# Micro_SD_Block.net
KiCad netlist of a schematic drawn in EAGLE
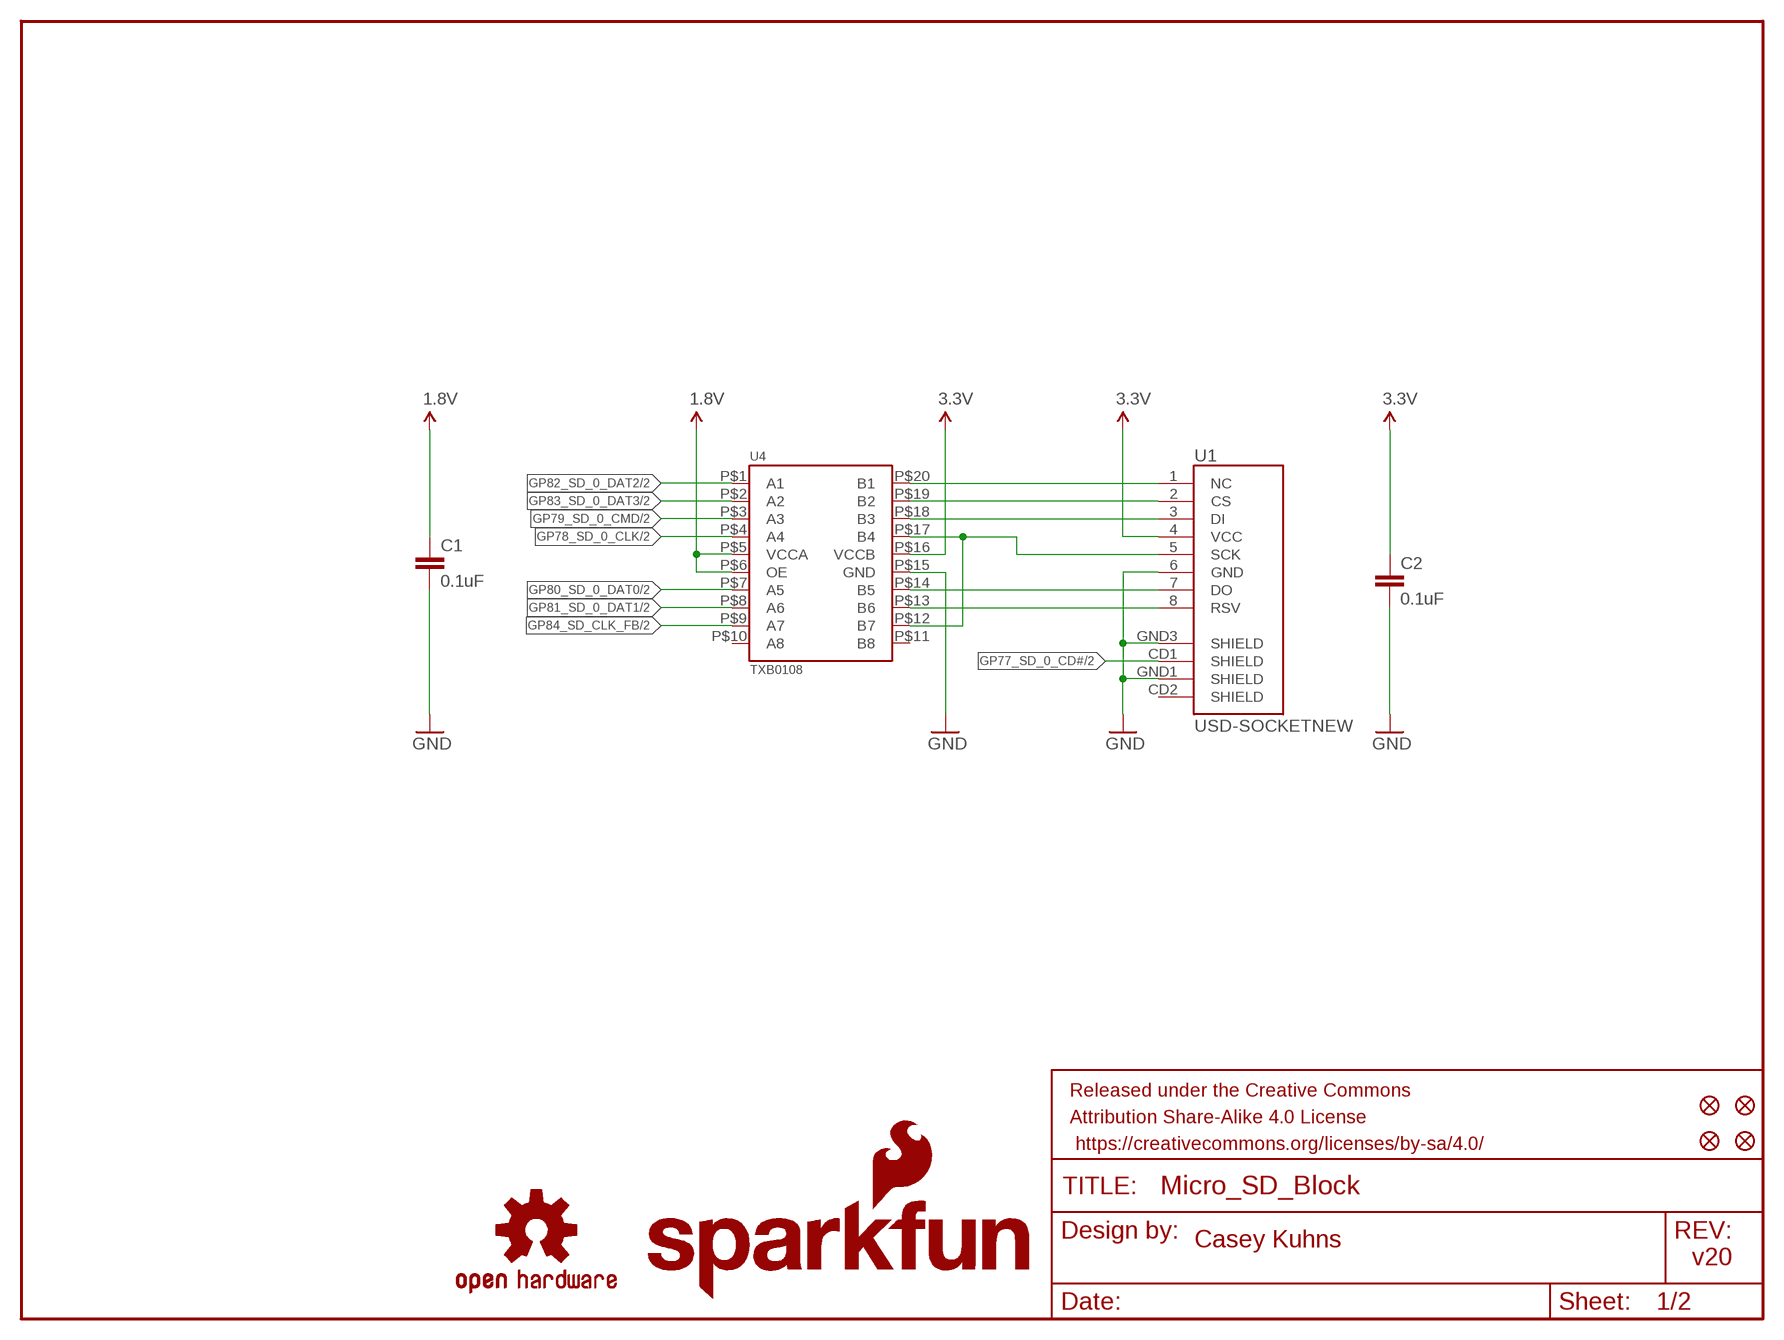
[diagram p0: schematic, sheet 1]
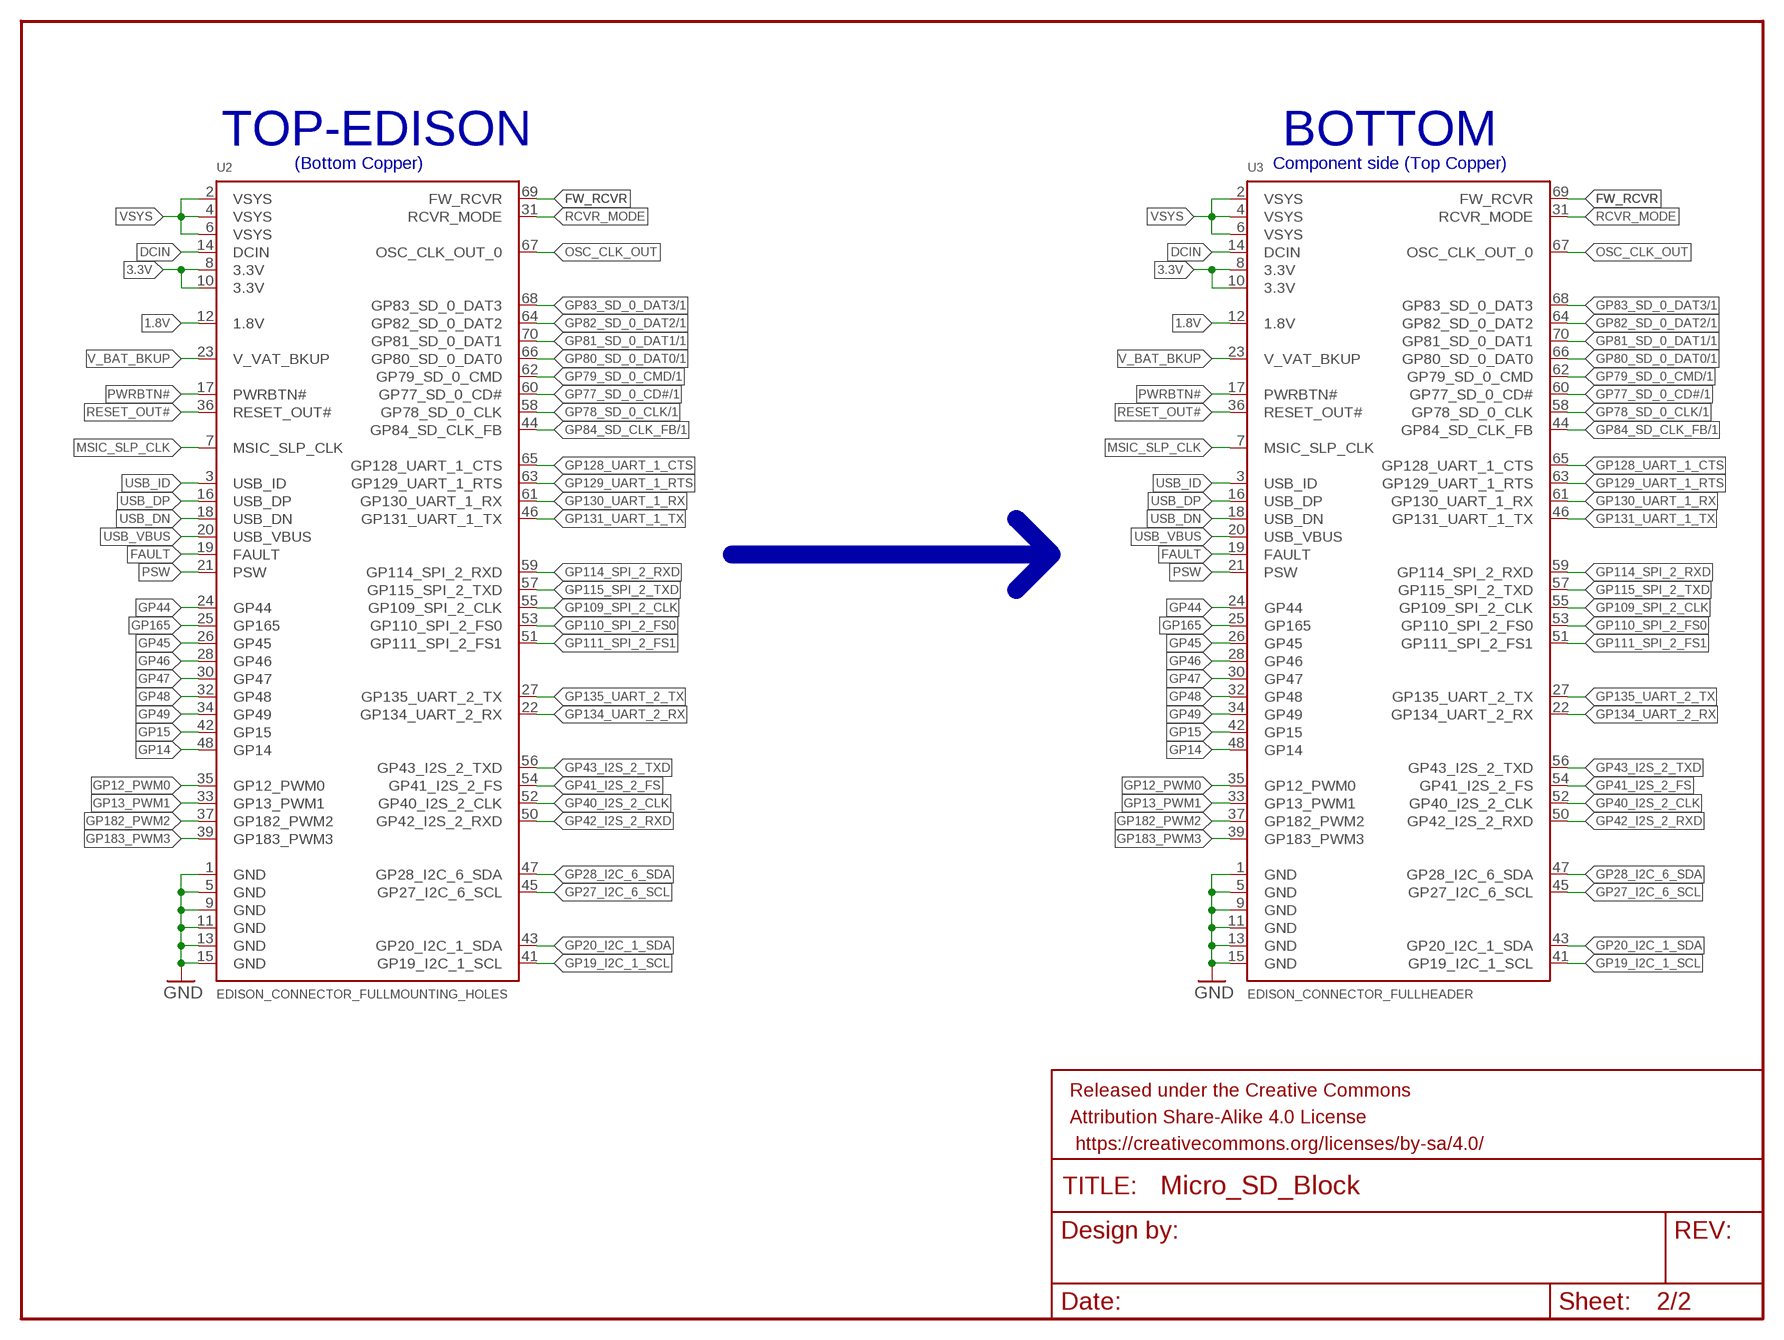
[diagram p1: schematic, sheet 2]

(export (version "E")
  (design (tool "Eeschema 10.0.6"))
  (components
    (comp (ref "C1")
      (value "0.1uF")
      (footprint "eagle-import:0603-CAP")
      (libsource (lib "eagle-import") (part "0.1UF-25V(+80/-20%)(0603)"))
    )
    (comp (ref "C2")
      (value "0.1uF")
      (footprint "eagle-import:0603-CAP")
      (libsource (lib "eagle-import") (part "0.1UF-25V(+80/-20%)(0603)"))
    )
    (comp (ref "FID1")
      (value "FIDUCIAL1X2")
      (footprint "eagle-import:FIDUCIAL-1X2")
      (libsource (lib "eagle-import") (part "FIDUCIAL1X2"))
    )
    (comp (ref "FID2")
      (value "FIDUCIAL1X2")
      (footprint "eagle-import:FIDUCIAL-1X2")
      (libsource (lib "eagle-import") (part "FIDUCIAL1X2"))
    )
    (comp (ref "FID3")
      (value "FIDUCIAL1X2")
      (footprint "eagle-import:FIDUCIAL-1X2")
      (libsource (lib "eagle-import") (part "FIDUCIAL1X2"))
    )
    (comp (ref "FID4")
      (value "FIDUCIAL1X2")
      (footprint "eagle-import:FIDUCIAL-1X2")
      (libsource (lib "eagle-import") (part "FIDUCIAL1X2"))
    )
    (comp (ref "FRAME1")
      (value "FRAME-LETTER")
      (footprint "eagle-import:CREATIVE_COMMONS")
      (libsource (lib "eagle-import") (part "FRAME-LETTER"))
    )
    (comp (ref "LOGO1")
      (value "OSHW-LOGOS")
      (footprint "eagle-import:OSHW-LOGO-S")
      (libsource (lib "eagle-import") (part "OSHW-LOGOS"))
    )
    (comp (ref "LOGO4")
      (value "SFE_LOGO_NAME_FLAME.1_INCH")
      (footprint "eagle-import:SFE_LOGO_NAME_FLAME_.1")
      (libsource (lib "eagle-import") (part "SFE_LOGO_NAME_FLAME.1_INCH"))
    )
    (comp (ref "U1")
      (value "USD-SOCKETNEW")
      (footprint "eagle-import:MICRO-SD-SOCKET-PP")
      (libsource (lib "eagle-import") (part "USD-SOCKETNEW"))
    )
    (comp (ref "U4")
      (value "TXB0108")
      (footprint "eagle-import:UFDFN-20")
      (libsource (lib "eagle-import") (part "TXB0108"))
    )
    (comp (ref "FRAME2")
      (value "FRAME-LETTER")
      (footprint "eagle-import:CREATIVE_COMMONS")
      (libsource (lib "eagle-import") (part "FRAME-LETTER"))
    )
    (comp (ref "U2")
      (value "EDISON_CONNECTOR_FULLMOUNTING_HOLES")
      (footprint "eagle-import:EDISON_DAUGHTER")
      (libsource (lib "eagle-import") (part "EDISON_CONNECTOR_FULLMOUNTING_HOLES"))
    )
    (comp (ref "U3")
      (value "EDISON_CONNECTOR_FULLHEADER")
      (footprint "eagle-import:DF40C-70DP-0.4(51)")
      (libsource (lib "eagle-import") (part "EDISON_CONNECTOR_FULLHEADER"))
    )
  )
  (nets
    (net (code "1") (name "1.8V") (class "Default")
      (node (ref "C1") (pin "1") (pinfunction "1_1") (pintype "passive"))
      (node (ref "U2") (pin "12") (pinfunction "1.8V_12") (pintype "bidirectional"))
      (node (ref "U3") (pin "12") (pinfunction "1.8V_12") (pintype "bidirectional"))
      (node (ref "U4") (pin "P$5") (pinfunction "VCCA_P$5") (pintype "bidirectional"))
      (node (ref "U4") (pin "P$6") (pinfunction "OE_P$6") (pintype "bidirectional"))
    )
    (net (code "2") (name "3.3V") (class "Default")
      (node (ref "C2") (pin "1") (pinfunction "1_1") (pintype "passive"))
      (node (ref "U1") (pin "4") (pinfunction "VCC_4") (pintype "bidirectional"))
      (node (ref "U2") (pin "10") (pinfunction "3.3V_10") (pintype "bidirectional"))
      (node (ref "U2") (pin "8") (pinfunction "3.3V_8") (pintype "bidirectional"))
      (node (ref "U3") (pin "10") (pinfunction "3.3V_10") (pintype "bidirectional"))
      (node (ref "U3") (pin "8") (pinfunction "3.3V_8") (pintype "bidirectional"))
      (node (ref "U4") (pin "P$16") (pinfunction "VCCB_P$16") (pintype "bidirectional"))
    )
    (net (code "3") (name "DCIN") (class "Default")
      (node (ref "U2") (pin "14") (pinfunction "DCIN_14") (pintype "bidirectional"))
      (node (ref "U3") (pin "14") (pinfunction "DCIN_14") (pintype "bidirectional"))
    )
    (net (code "4") (name "FAULT") (class "Default")
      (node (ref "U2") (pin "19") (pinfunction "FAULT_19") (pintype "bidirectional"))
      (node (ref "U3") (pin "19") (pinfunction "FAULT_19") (pintype "bidirectional"))
    )
    (net (code "5") (name "FW_RCVR") (class "Default")
      (node (ref "U2") (pin "69") (pinfunction "FW_RCVR_69") (pintype "bidirectional"))
      (node (ref "U3") (pin "69") (pinfunction "FW_RCVR_69") (pintype "bidirectional"))
    )
    (net (code "6") (name "GND") (class "Default")
      (node (ref "C1") (pin "2") (pinfunction "2_2") (pintype "passive"))
      (node (ref "C2") (pin "2") (pinfunction "2_2") (pintype "passive"))
      (node (ref "U1") (pin "6") (pinfunction "GND_6") (pintype "bidirectional"))
      (node (ref "U1") (pin "GND1") (pinfunction "SHIELD_GND1") (pintype "bidirectional"))
      (node (ref "U1") (pin "GND3") (pinfunction "SHIELD_GND3") (pintype "bidirectional"))
      (node (ref "U2") (pin "1") (pinfunction "GND_1") (pintype "bidirectional"))
      (node (ref "U2") (pin "11") (pinfunction "GND_11") (pintype "bidirectional"))
      (node (ref "U2") (pin "13") (pinfunction "GND_13") (pintype "bidirectional"))
      (node (ref "U2") (pin "15") (pinfunction "GND_15") (pintype "bidirectional"))
      (node (ref "U2") (pin "5") (pinfunction "GND_5") (pintype "bidirectional"))
      (node (ref "U2") (pin "9") (pinfunction "GND_9") (pintype "bidirectional"))
      (node (ref "U3") (pin "1") (pinfunction "GND_1") (pintype "bidirectional"))
      (node (ref "U3") (pin "11") (pinfunction "GND_11") (pintype "bidirectional"))
      (node (ref "U3") (pin "13") (pinfunction "GND_13") (pintype "bidirectional"))
      (node (ref "U3") (pin "15") (pinfunction "GND_15") (pintype "bidirectional"))
      (node (ref "U3") (pin "5") (pinfunction "GND_5") (pintype "bidirectional"))
      (node (ref "U3") (pin "9") (pinfunction "GND_9") (pintype "bidirectional"))
      (node (ref "U4") (pin "P$15") (pinfunction "GND_P$15") (pintype "bidirectional"))
    )
    (net (code "7") (name "GP12_PWM0") (class "Default")
      (node (ref "U2") (pin "35") (pinfunction "GP12_PWM0_35") (pintype "bidirectional"))
      (node (ref "U3") (pin "35") (pinfunction "GP12_PWM0_35") (pintype "bidirectional"))
    )
    (net (code "8") (name "GP13_PWM1") (class "Default")
      (node (ref "U2") (pin "33") (pinfunction "GP13_PWM1_33") (pintype "bidirectional"))
      (node (ref "U3") (pin "33") (pinfunction "GP13_PWM1_33") (pintype "bidirectional"))
    )
    (net (code "9") (name "GP14") (class "Default")
      (node (ref "U2") (pin "48") (pinfunction "GP14_48") (pintype "bidirectional"))
      (node (ref "U3") (pin "48") (pinfunction "GP14_48") (pintype "bidirectional"))
    )
    (net (code "10") (name "GP15") (class "Default")
      (node (ref "U2") (pin "42") (pinfunction "GP15_42") (pintype "bidirectional"))
      (node (ref "U3") (pin "42") (pinfunction "GP15_42") (pintype "bidirectional"))
    )
    (net (code "11") (name "GP19_I2C_1_SCL") (class "Default")
      (node (ref "U2") (pin "41") (pinfunction "GP19_I2C_1_SCL_41") (pintype "bidirectional"))
      (node (ref "U3") (pin "41") (pinfunction "GP19_I2C_1_SCL_41") (pintype "bidirectional"))
    )
    (net (code "12") (name "GP20_I2C_1_SDA") (class "Default")
      (node (ref "U2") (pin "43") (pinfunction "GP20_I2C_1_SDA_43") (pintype "bidirectional"))
      (node (ref "U3") (pin "43") (pinfunction "GP20_I2C_1_SDA_43") (pintype "bidirectional"))
    )
    (net (code "13") (name "GP27_I2C_6_SCL") (class "Default")
      (node (ref "U2") (pin "45") (pinfunction "GP27_I2C_6_SCL_45") (pintype "bidirectional"))
      (node (ref "U3") (pin "45") (pinfunction "GP27_I2C_6_SCL_45") (pintype "bidirectional"))
    )
    (net (code "14") (name "GP28_I2C_6_SDA") (class "Default")
      (node (ref "U2") (pin "47") (pinfunction "GP28_I2C_6_SDA_47") (pintype "bidirectional"))
      (node (ref "U3") (pin "47") (pinfunction "GP28_I2C_6_SDA_47") (pintype "bidirectional"))
    )
    (net (code "15") (name "GP40_I2S_2_CLK") (class "Default")
      (node (ref "U2") (pin "52") (pinfunction "GP40_I2S_2_CLK_52") (pintype "bidirectional"))
      (node (ref "U3") (pin "52") (pinfunction "GP40_I2S_2_CLK_52") (pintype "bidirectional"))
    )
    (net (code "16") (name "GP41_I2S_2_FS") (class "Default")
      (node (ref "U2") (pin "54") (pinfunction "GP41_I2S_2_FS_54") (pintype "bidirectional"))
      (node (ref "U3") (pin "54") (pinfunction "GP41_I2S_2_FS_54") (pintype "bidirectional"))
    )
    (net (code "17") (name "GP42_I2S_2_RXD") (class "Default")
      (node (ref "U2") (pin "50") (pinfunction "GP42_I2S_2_RXD_50") (pintype "bidirectional"))
      (node (ref "U3") (pin "50") (pinfunction "GP42_I2S_2_RXD_50") (pintype "bidirectional"))
    )
    (net (code "18") (name "GP43_I2S_2_TXD") (class "Default")
      (node (ref "U2") (pin "56") (pinfunction "GP43_I2S_2_TXD_56") (pintype "bidirectional"))
      (node (ref "U3") (pin "56") (pinfunction "GP43_I2S_2_TXD_56") (pintype "bidirectional"))
    )
    (net (code "19") (name "GP44") (class "Default")
      (node (ref "U2") (pin "24") (pinfunction "GP44_24") (pintype "bidirectional"))
      (node (ref "U3") (pin "24") (pinfunction "GP44_24") (pintype "bidirectional"))
    )
    (net (code "20") (name "GP45") (class "Default")
      (node (ref "U2") (pin "26") (pinfunction "GP45_26") (pintype "bidirectional"))
      (node (ref "U3") (pin "26") (pinfunction "GP45_26") (pintype "bidirectional"))
    )
    (net (code "21") (name "GP46") (class "Default")
      (node (ref "U2") (pin "28") (pinfunction "GP46_28") (pintype "bidirectional"))
      (node (ref "U3") (pin "28") (pinfunction "GP46_28") (pintype "bidirectional"))
    )
    (net (code "22") (name "GP47") (class "Default")
      (node (ref "U2") (pin "30") (pinfunction "GP47_30") (pintype "bidirectional"))
      (node (ref "U3") (pin "30") (pinfunction "GP47_30") (pintype "bidirectional"))
    )
    (net (code "23") (name "GP48") (class "Default")
      (node (ref "U2") (pin "32") (pinfunction "GP48_32") (pintype "bidirectional"))
      (node (ref "U3") (pin "32") (pinfunction "GP48_32") (pintype "bidirectional"))
    )
    (net (code "24") (name "GP49") (class "Default")
      (node (ref "U2") (pin "34") (pinfunction "GP49_34") (pintype "bidirectional"))
      (node (ref "U3") (pin "34") (pinfunction "GP49_34") (pintype "bidirectional"))
    )
    (net (code "25") (name "GP77_SD_0_CD#") (class "Default")
      (node (ref "U1") (pin "CD1") (pinfunction "SHIELD_CD1") (pintype "bidirectional"))
      (node (ref "U2") (pin "60") (pinfunction "GP77_SD_0_CD#_60") (pintype "bidirectional"))
      (node (ref "U3") (pin "60") (pinfunction "GP77_SD_0_CD#_60") (pintype "bidirectional"))
    )
    (net (code "26") (name "GP78_SD_0_CLK") (class "Default")
      (node (ref "U2") (pin "58") (pinfunction "GP78_SD_0_CLK_58") (pintype "bidirectional"))
      (node (ref "U3") (pin "58") (pinfunction "GP78_SD_0_CLK_58") (pintype "bidirectional"))
      (node (ref "U4") (pin "P$4") (pinfunction "A4_P$4") (pintype "bidirectional"))
    )
    (net (code "27") (name "GP79_SD_0_CMD") (class "Default")
      (node (ref "U2") (pin "62") (pinfunction "GP79_SD_0_CMD_62") (pintype "bidirectional"))
      (node (ref "U3") (pin "62") (pinfunction "GP79_SD_0_CMD_62") (pintype "bidirectional"))
      (node (ref "U4") (pin "P$3") (pinfunction "A3_P$3") (pintype "bidirectional"))
    )
    (net (code "28") (name "GP80_SD_0_DAT0") (class "Default")
      (node (ref "U2") (pin "66") (pinfunction "GP80_SD_0_DAT0_66") (pintype "bidirectional"))
      (node (ref "U3") (pin "66") (pinfunction "GP80_SD_0_DAT0_66") (pintype "bidirectional"))
      (node (ref "U4") (pin "P$7") (pinfunction "A5_P$7") (pintype "bidirectional"))
    )
    (net (code "29") (name "GP81_SD_0_DAT1") (class "Default")
      (node (ref "U2") (pin "70") (pinfunction "GP81_SD_0_DAT1_70") (pintype "bidirectional"))
      (node (ref "U3") (pin "70") (pinfunction "GP81_SD_0_DAT1_70") (pintype "bidirectional"))
      (node (ref "U4") (pin "P$8") (pinfunction "A6_P$8") (pintype "bidirectional"))
    )
    (net (code "30") (name "GP82_SD_0_DAT2") (class "Default")
      (node (ref "U2") (pin "64") (pinfunction "GP82_SD_0_DAT2_64") (pintype "bidirectional"))
      (node (ref "U3") (pin "64") (pinfunction "GP82_SD_0_DAT2_64") (pintype "bidirectional"))
      (node (ref "U4") (pin "P$1") (pinfunction "A1_P$1") (pintype "bidirectional"))
    )
    (net (code "31") (name "GP83_SD_0_DAT3") (class "Default")
      (node (ref "U2") (pin "68") (pinfunction "GP83_SD_0_DAT3_68") (pintype "bidirectional"))
      (node (ref "U3") (pin "68") (pinfunction "GP83_SD_0_DAT3_68") (pintype "bidirectional"))
      (node (ref "U4") (pin "P$2") (pinfunction "A2_P$2") (pintype "bidirectional"))
    )
    (net (code "32") (name "GP84_SD_CLK_FB") (class "Default")
      (node (ref "U2") (pin "44") (pinfunction "GP84_SD_CLK_FB_44") (pintype "bidirectional"))
      (node (ref "U3") (pin "44") (pinfunction "GP84_SD_CLK_FB_44") (pintype "bidirectional"))
      (node (ref "U4") (pin "P$9") (pinfunction "A7_P$9") (pintype "bidirectional"))
    )
    (net (code "33") (name "GP109_SPI_2_CLK") (class "Default")
      (node (ref "U2") (pin "55") (pinfunction "GP109_SPI_2_CLK_55") (pintype "bidirectional"))
      (node (ref "U3") (pin "55") (pinfunction "GP109_SPI_2_CLK_55") (pintype "bidirectional"))
    )
    (net (code "34") (name "GP110_SPI_2_FS0") (class "Default")
      (node (ref "U2") (pin "53") (pinfunction "GP110_SPI_2_FS0_53") (pintype "bidirectional"))
      (node (ref "U3") (pin "53") (pinfunction "GP110_SPI_2_FS0_53") (pintype "bidirectional"))
    )
    (net (code "35") (name "GP111_SPI_2_FS1") (class "Default")
      (node (ref "U2") (pin "51") (pinfunction "GP111_SPI_2_FS1_51") (pintype "bidirectional"))
      (node (ref "U3") (pin "51") (pinfunction "GP111_SPI_2_FS1_51") (pintype "bidirectional"))
    )
    (net (code "36") (name "GP114_SPI_2_RXD") (class "Default")
      (node (ref "U2") (pin "59") (pinfunction "GP114_SPI_2_RXD_59") (pintype "bidirectional"))
      (node (ref "U3") (pin "59") (pinfunction "GP114_SPI_2_RXD_59") (pintype "bidirectional"))
    )
    (net (code "37") (name "GP115_SPI_2_TXD") (class "Default")
      (node (ref "U2") (pin "57") (pinfunction "GP115_SPI_2_TXD_57") (pintype "bidirectional"))
      (node (ref "U3") (pin "57") (pinfunction "GP115_SPI_2_TXD_57") (pintype "bidirectional"))
    )
    (net (code "38") (name "GP128_UART_1_CTS") (class "Default")
      (node (ref "U2") (pin "65") (pinfunction "GP128_UART_1_CTS_65") (pintype "bidirectional"))
      (node (ref "U3") (pin "65") (pinfunction "GP128_UART_1_CTS_65") (pintype "bidirectional"))
    )
    (net (code "39") (name "GP129_UART_1_RTS") (class "Default")
      (node (ref "U2") (pin "63") (pinfunction "GP129_UART_1_RTS_63") (pintype "bidirectional"))
      (node (ref "U3") (pin "63") (pinfunction "GP129_UART_1_RTS_63") (pintype "bidirectional"))
    )
    (net (code "40") (name "GP130_UART_1_RX") (class "Default")
      (node (ref "U2") (pin "61") (pinfunction "GP130_UART_1_RX_61") (pintype "bidirectional"))
      (node (ref "U3") (pin "61") (pinfunction "GP130_UART_1_RX_61") (pintype "bidirectional"))
    )
    (net (code "41") (name "GP131_UART_1_TX") (class "Default")
      (node (ref "U2") (pin "46") (pinfunction "GP131_UART_1_TX_46") (pintype "bidirectional"))
      (node (ref "U3") (pin "46") (pinfunction "GP131_UART_1_TX_46") (pintype "bidirectional"))
    )
    (net (code "42") (name "GP134_UART_2_RX") (class "Default")
      (node (ref "U2") (pin "22") (pinfunction "GP134_UART_2_RX_22") (pintype "bidirectional"))
      (node (ref "U3") (pin "22") (pinfunction "GP134_UART_2_RX_22") (pintype "bidirectional"))
    )
    (net (code "43") (name "GP135_UART_2_TX") (class "Default")
      (node (ref "U2") (pin "27") (pinfunction "GP135_UART_2_TX_27") (pintype "bidirectional"))
      (node (ref "U3") (pin "27") (pinfunction "GP135_UART_2_TX_27") (pintype "bidirectional"))
    )
    (net (code "44") (name "GP165") (class "Default")
      (node (ref "U2") (pin "25") (pinfunction "GP165_25") (pintype "bidirectional"))
      (node (ref "U3") (pin "25") (pinfunction "GP165_25") (pintype "bidirectional"))
    )
    (net (code "45") (name "GP182_PWM2") (class "Default")
      (node (ref "U2") (pin "37") (pinfunction "GP182_PWM2_37") (pintype "bidirectional"))
      (node (ref "U3") (pin "37") (pinfunction "GP182_PWM2_37") (pintype "bidirectional"))
    )
    (net (code "46") (name "GP183_PWM3") (class "Default")
      (node (ref "U2") (pin "39") (pinfunction "GP183_PWM3_39") (pintype "bidirectional"))
      (node (ref "U3") (pin "39") (pinfunction "GP183_PWM3_39") (pintype "bidirectional"))
    )
    (net (code "47") (name "MSIC_SLP_CLK") (class "Default")
      (node (ref "U2") (pin "7") (pinfunction "MSIC_SLP_CLK_7") (pintype "bidirectional"))
      (node (ref "U3") (pin "7") (pinfunction "MSIC_SLP_CLK_7") (pintype "bidirectional"))
    )
    (net (code "48") (name "Net-(U1-CS)") (class "Default")
      (node (ref "U1") (pin "2") (pinfunction "CS_2") (pintype "bidirectional"))
      (node (ref "U4") (pin "P$19") (pinfunction "B2_P$19") (pintype "bidirectional"))
    )
    (net (code "49") (name "Net-(U1-DI)") (class "Default")
      (node (ref "U1") (pin "3") (pinfunction "DI_3") (pintype "bidirectional"))
      (node (ref "U4") (pin "P$18") (pinfunction "B3_P$18") (pintype "bidirectional"))
    )
    (net (code "50") (name "Net-(U1-DO)") (class "Default")
      (node (ref "U1") (pin "7") (pinfunction "DO_7") (pintype "bidirectional"))
      (node (ref "U4") (pin "P$14") (pinfunction "B5_P$14") (pintype "bidirectional"))
    )
    (net (code "51") (name "Net-(U1-NC)") (class "Default")
      (node (ref "U1") (pin "1") (pinfunction "NC_1") (pintype "bidirectional"))
      (node (ref "U4") (pin "P$20") (pinfunction "B1_P$20") (pintype "bidirectional"))
    )
    (net (code "52") (name "Net-(U1-RSV)") (class "Default")
      (node (ref "U1") (pin "8") (pinfunction "RSV_8") (pintype "bidirectional"))
      (node (ref "U4") (pin "P$13") (pinfunction "B6_P$13") (pintype "bidirectional"))
    )
    (net (code "53") (name "Net-(U1-SCK)") (class "Default")
      (node (ref "U1") (pin "5") (pinfunction "SCK_5") (pintype "bidirectional"))
      (node (ref "U4") (pin "P$12") (pinfunction "B7_P$12") (pintype "bidirectional"))
      (node (ref "U4") (pin "P$17") (pinfunction "B4_P$17") (pintype "bidirectional"))
    )
    (net (code "54") (name "OSC_CLK_OUT") (class "Default")
      (node (ref "U2") (pin "67") (pinfunction "OSC_CLK_OUT_0_67") (pintype "bidirectional"))
      (node (ref "U3") (pin "67") (pinfunction "OSC_CLK_OUT_0_67") (pintype "bidirectional"))
    )
    (net (code "55") (name "PSW") (class "Default")
      (node (ref "U2") (pin "21") (pinfunction "PSW_21") (pintype "bidirectional"))
      (node (ref "U3") (pin "21") (pinfunction "PSW_21") (pintype "bidirectional"))
    )
    (net (code "56") (name "PWRBTN#") (class "Default")
      (node (ref "U2") (pin "17") (pinfunction "PWRBTN#_17") (pintype "bidirectional"))
      (node (ref "U3") (pin "17") (pinfunction "PWRBTN#_17") (pintype "bidirectional"))
    )
    (net (code "57") (name "RCVR_MODE") (class "Default")
      (node (ref "U2") (pin "31") (pinfunction "RCVR_MODE_31") (pintype "bidirectional"))
      (node (ref "U3") (pin "31") (pinfunction "RCVR_MODE_31") (pintype "bidirectional"))
    )
    (net (code "58") (name "RESET_OUT#") (class "Default")
      (node (ref "U2") (pin "36") (pinfunction "RESET_OUT#_36") (pintype "bidirectional"))
      (node (ref "U3") (pin "36") (pinfunction "RESET_OUT#_36") (pintype "bidirectional"))
    )
    (net (code "59") (name "USB_DN") (class "Default")
      (node (ref "U2") (pin "18") (pinfunction "USB_DN_18") (pintype "bidirectional"))
      (node (ref "U3") (pin "18") (pinfunction "USB_DN_18") (pintype "bidirectional"))
    )
    (net (code "60") (name "USB_DP") (class "Default")
      (node (ref "U2") (pin "16") (pinfunction "USB_DP_16") (pintype "bidirectional"))
      (node (ref "U3") (pin "16") (pinfunction "USB_DP_16") (pintype "bidirectional"))
    )
    (net (code "61") (name "USB_ID") (class "Default")
      (node (ref "U2") (pin "3") (pinfunction "USB_ID_3") (pintype "bidirectional"))
      (node (ref "U3") (pin "3") (pinfunction "USB_ID_3") (pintype "bidirectional"))
    )
    (net (code "62") (name "USB_VBUS") (class "Default")
      (node (ref "U2") (pin "20") (pinfunction "USB_VBUS_20") (pintype "bidirectional"))
      (node (ref "U3") (pin "20") (pinfunction "USB_VBUS_20") (pintype "bidirectional"))
    )
    (net (code "63") (name "VSYS") (class "Default")
      (node (ref "U2") (pin "2") (pinfunction "VSYS_2") (pintype "bidirectional"))
      (node (ref "U2") (pin "4") (pinfunction "VSYS_4") (pintype "bidirectional"))
      (node (ref "U2") (pin "6") (pinfunction "VSYS_6") (pintype "bidirectional"))
      (node (ref "U3") (pin "2") (pinfunction "VSYS_2") (pintype "bidirectional"))
      (node (ref "U3") (pin "4") (pinfunction "VSYS_4") (pintype "bidirectional"))
      (node (ref "U3") (pin "6") (pinfunction "VSYS_6") (pintype "bidirectional"))
    )
    (net (code "64") (name "V_BAT_BKUP") (class "Default")
      (node (ref "U2") (pin "23") (pinfunction "V_VAT_BKUP_23") (pintype "bidirectional"))
      (node (ref "U3") (pin "23") (pinfunction "V_VAT_BKUP_23") (pintype "bidirectional"))
    )
    (net (code "65") (name "unconnected-(U1-SHIELD-PadCD2)") (class "Default")
      (node (ref "U1") (pin "CD2") (pinfunction "SHIELD_CD2") (pintype "bidirectional"))
    )
    (net (code "66") (name "unconnected-(U4-A8-PadP$10)") (class "Default")
      (node (ref "U4") (pin "P$10") (pinfunction "A8_P$10") (pintype "bidirectional"))
    )
    (net (code "67") (name "unconnected-(U4-B8-PadP$11)") (class "Default")
      (node (ref "U4") (pin "P$11") (pinfunction "B8_P$11") (pintype "bidirectional"))
    )
  )
)
